# DM1095_USB.net
KiCad netlist of a schematic drawn in Altium Designer
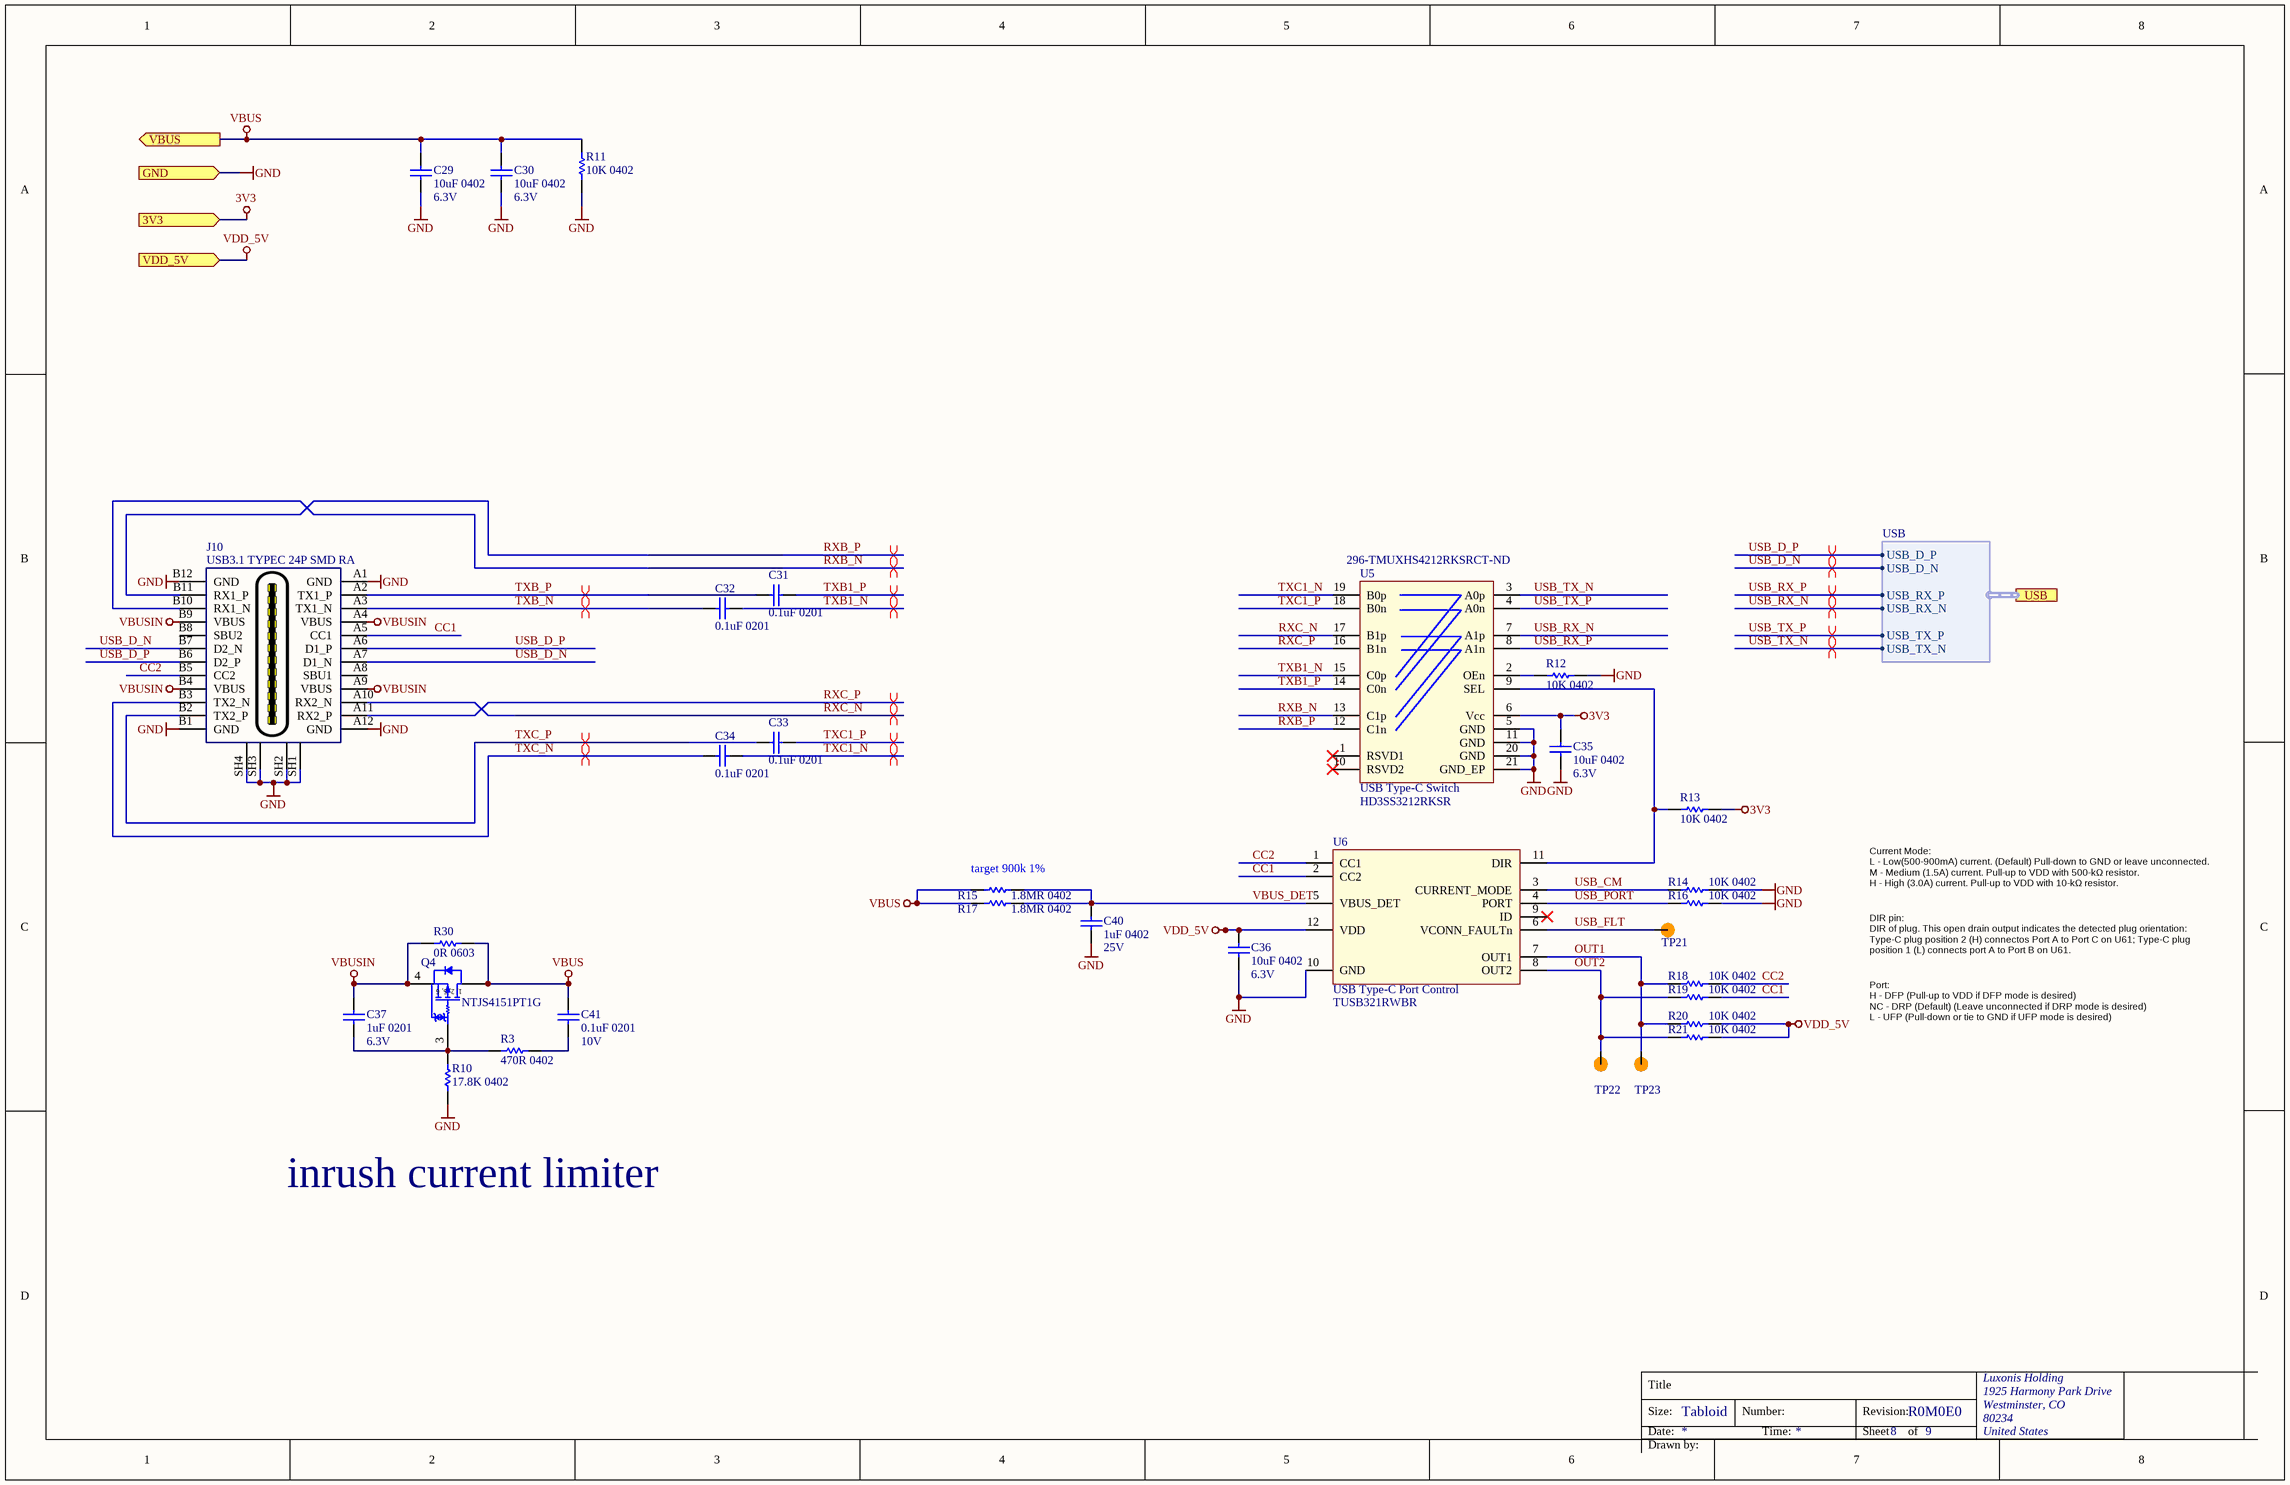
[diagram p0: DM1095_USB.SchDoc]

(export (version "E")
  (design (tool "Eeschema 10.0.6"))
  (components
    (comp (ref "C29")
      (value "10uF 0402")
      (footprint "CAP_Altium_Vault_Generic:CAPC0402(1005)70_L")
      (description "CAP CER 10UF 6.3V X5R 0402 20%")
      (fields (field (name "TOLERANCE") "20%") (field (name "VOLTAGE RATING") "6.3V"))
      (libsource (lib "LuxonisMaster") (part "GRM155R60J106ME15D"))
    )
    (comp (ref "C30")
      (value "10uF 0402")
      (footprint "CAP_Altium_Vault_Generic:CAPC0402(1005)70_L")
      (description "CAP CER 10UF 6.3V X5R 0402 20%")
      (fields (field (name "TOLERANCE") "20%") (field (name "VOLTAGE RATING") "6.3V"))
      (libsource (lib "LuxonisMaster") (part "GRM155R60J106ME15D"))
    )
    (comp (ref "C31")
      (value "0.1uF 0201")
      (footprint "CAP_Altium_Vault_Generic:CAPC0201(0603)33_L")
      (description "CAP CER 0.1UF 10V X5R 0201")
      (fields (field (name "TOLERANCE") "10%") (field (name "VOLTAGE") "10V"))
      (libsource (lib "LuxonisMaster") (part "GRM033R61A104KE15D"))
    )
    (comp (ref "C32")
      (value "0.1uF 0201")
      (footprint "CAP_Altium_Vault_Generic:CAPC0201(0603)33_L")
      (description "CAP CER 0.1UF 10V X5R 0201")
      (fields (field (name "TOLERANCE") "10%") (field (name "VOLTAGE") "10V"))
      (libsource (lib "LuxonisMaster") (part "GRM033R61A104KE15D"))
    )
    (comp (ref "C33")
      (value "0.1uF 0201")
      (footprint "CAP_Altium_Vault_Generic:CAPC0201(0603)33_L")
      (description "CAP CER 0.1UF 10V X5R 0201")
      (fields (field (name "TOLERANCE") "10%") (field (name "VOLTAGE") "10V"))
      (libsource (lib "LuxonisMaster") (part "GRM033R61A104KE15D"))
    )
    (comp (ref "C34")
      (value "0.1uF 0201")
      (footprint "CAP_Altium_Vault_Generic:CAPC0201(0603)33_L")
      (description "CAP CER 0.1UF 10V X5R 0201")
      (fields (field (name "TOLERANCE") "10%") (field (name "VOLTAGE") "10V"))
      (libsource (lib "LuxonisMaster") (part "GRM033R61A104KE15D"))
    )
    (comp (ref "C35")
      (value "10uF 0402")
      (footprint "CAP_Altium_Vault_Generic:CAPC0402(1005)70_L")
      (description "CAP CER 10UF 6.3V X5R 0402 20%")
      (fields (field (name "TOLERANCE") "20%") (field (name "VOLTAGE RATING") "6.3V"))
      (libsource (lib "LuxonisMaster") (part "GRM155R60J106ME15D"))
    )
    (comp (ref "C36")
      (value "10uF 0402")
      (footprint "CAP_Altium_Vault_Generic:CAPC0402(1005)70_L")
      (description "CAP CER 10UF 6.3V X5R 0402 20%")
      (fields (field (name "TOLERANCE") "20%") (field (name "VOLTAGE RATING") "6.3V"))
      (libsource (lib "LuxonisMaster") (part "GRM155R60J106ME15D"))
    )
    (comp (ref "C37")
      (value "1uF 0201")
      (footprint "CAP_Altium_Vault_Generic:CAPC0201(0603)33_N")
      (description "CAP CER 1UF 6.3V X5R 0201 20%")
      (fields (field (name "TOLERANCE") "20%") (field (name "VOLTAGE") "6.3V"))
      (libsource (lib "LuxonisMaster") (part "GRM033R60J105MEA2D"))
    )
    (comp (ref "C40")
      (value "1uF 0402")
      (footprint "CAP_Altium_Vault_Generic:CAPC0402(1005)70_N")
      (description "CAP CER 1UF 25V X5R 0402 10%")
      (fields
        (field (name "TOLERANCE") "10%")
        (field (name "VOLTAGE") "25V")
        (field (name "VOLTAGE RATING") "25V")
      )
      (libsource (lib "LuxonisMaster") (part "GRM155R61E105KA12D"))
    )
    (comp (ref "C41")
      (value "0.1uF 0201")
      (footprint "CAP_Altium_Vault_Generic:CAPC0201(0603)33_N")
      (description "CAP CER 0.1UF 10V X5R 0201")
      (fields (field (name "TOLERANCE") "10%") (field (name "VOLTAGE") "10V"))
      (libsource (lib "LuxonisMaster") (part "GRM033R61A104KE15D"))
    )
    (comp (ref "J10")
      (value "USB3.1 TYPEC 24P SMD RA")
      (footprint "LuxonisMaster:105450-0101")
      (description "CONN RCP USB3.1 TYPEC 24P SMD RA")
      (libsource (lib "LuxonisMaster") (part "105450-0101"))
    )
    (comp (ref "Q4")
      (value "NTJS4151PT1G")
      (footprint "ONSC-SC70-6-419B-02_W_V")
      (description "Trench Power MOSFET, -20 V, -4.2 A, Single P-Channel, 6-Pin SC70, Pb-Free, Tape and Reel")
      (libsource (lib "DM1095") (part "NTJS4151PT1G"))
    )
    (comp (ref "R3")
      (value "470R 0402")
      (footprint "RES_Altium_Vault_Generic:RESC0402(1005)_L")
      (description "RES SMD 470 OHM 1% 1/16W 0402")
      (fields (field (name "TOLERANCE") "1%"))
      (libsource (lib "LuxonisMaster") (part "CRCW0402470RFKED"))
    )
    (comp (ref "R10")
      (value "17.8K 0402")
      (footprint "RES_Altium_Vault_Generic:RESC0402(1005)_L")
      (fields (field (name "TOLERANCE") "1%"))
      (libsource (lib "LuxonisMaster") (part "ERJ-2RKF1782X"))
    )
    (comp (ref "R11")
      (value "10K 0402")
      (footprint "RES_Altium_Vault_Generic:RESC0402(1005)_L")
      (fields (field (name "TOLERANCE") "1%"))
      (libsource (lib "LuxonisMaster") (part "RC0402FR-1310KL"))
    )
    (comp (ref "R12")
      (value "10K 0402")
      (footprint "RES_Altium_Vault_Generic:RESC0402(1005)_L")
      (fields (field (name "TOLERANCE") "1%"))
      (libsource (lib "LuxonisMaster") (part "RC0402FR-1310KL"))
    )
    (comp (ref "R13")
      (value "10K 0402")
      (footprint "RES_Altium_Vault_Generic:RESC0402(1005)_L")
      (fields (field (name "TOLERANCE") "1%"))
      (libsource (lib "LuxonisMaster") (part "RC0402FR-1310KL"))
    )
    (comp (ref "R14")
      (value "10K 0402")
      (footprint "RES_Altium_Vault_Generic:RESC0402(1005)_L")
      (fields (field (name "TOLERANCE") "1%"))
      (libsource (lib "LuxonisMaster") (part "RC0402FR-1310KL"))
    )
    (comp (ref "R15")
      (value "1.8MR 0402")
      (footprint "RES_Altium_Vault_Generic:RESC0402(1005)_L")
      (description "RES SMD 1.8M OHM 1% 1/16W 0402")
      (fields (field (name "TOLERANCE") "1%"))
      (libsource (lib "LuxonisMaster") (part "CRCW04021M80FKED"))
    )
    (comp (ref "R16")
      (value "10K 0402")
      (footprint "RES_Altium_Vault_Generic:RESC0402(1005)_L")
      (fields (field (name "TOLERANCE") "1%"))
      (libsource (lib "LuxonisMaster") (part "RC0402FR-1310KL"))
    )
    (comp (ref "R17")
      (value "1.8MR 0402")
      (footprint "RES_Altium_Vault_Generic:RESC0402(1005)_L")
      (description "RES SMD 1.8M OHM 1% 1/16W 0402")
      (fields (field (name "TOLERANCE") "1%"))
      (libsource (lib "LuxonisMaster") (part "CRCW04021M80FKED"))
    )
    (comp (ref "R18")
      (value "10K 0402")
      (footprint "RES_Altium_Vault_Generic:RESC0402(1005)_L")
      (fields (field (name "TOLERANCE") "1%"))
      (libsource (lib "LuxonisMaster") (part "RC0402FR-1310KL"))
    )
    (comp (ref "R19")
      (value "10K 0402")
      (footprint "RES_Altium_Vault_Generic:RESC0402(1005)_L")
      (fields (field (name "TOLERANCE") "1%"))
      (libsource (lib "LuxonisMaster") (part "RC0402FR-1310KL"))
    )
    (comp (ref "R20")
      (value "10K 0402")
      (footprint "RES_Altium_Vault_Generic:RESC0402(1005)_L")
      (fields (field (name "TOLERANCE") "1%"))
      (libsource (lib "LuxonisMaster") (part "RC0402FR-1310KL"))
    )
    (comp (ref "R21")
      (value "10K 0402")
      (footprint "RES_Altium_Vault_Generic:RESC0402(1005)_L")
      (fields (field (name "TOLERANCE") "1%"))
      (libsource (lib "LuxonisMaster") (part "RC0402FR-1310KL"))
    )
    (comp (ref "R30")
      (value "0R 0603")
      (footprint "RES_Altium_Vault_Generic:RESC0603(1608)_N")
      (fields (field (name "TOLERANCE") "5%"))
      (libsource (lib "LuxonisMaster") (part "CRCW06030000Z0EA"))
    )
    (comp (ref "TP21")
      (value "TP100_200_NS")
      (footprint "LuxonisMaster:TP100_200_NS")
      (libsource (lib "LuxonisMaster") (part "TEST_POINT"))
    )
    (comp (ref "TP22")
      (value "TP100_200_NS")
      (footprint "LuxonisMaster:TP100_200_NS")
      (libsource (lib "LuxonisMaster") (part "TEST_POINT"))
    )
    (comp (ref "TP23")
      (value "TP100_200_NS")
      (footprint "LuxonisMaster:TP100_200_NS")
      (libsource (lib "LuxonisMaster") (part "TEST_POINT"))
    )
    (comp (ref "U5")
      (value "USB Type-C Switch")
      (footprint "LuxonisMaster:HD3SS3212RKSR")
      (description "Differential Multiplexer, 1 Func, 2 Channel, PQCC20")
      (fields
        (field (name "MANUFACTURER PART NUMBER 1") "HD3SS3212RKSR")
        (field (name "SUPPLIER PART NUMBER 2") "296-TMUXHS4212RKSRCT-ND")
      )
      (libsource (lib "LuxonisMaster") (part "HD3SS3212RKSR"))
    )
    (comp (ref "U6")
      (value "USB Type-C Port Control")
      (footprint "LuxonisMaster:TUSB321RWBR")
      (description "IC USB PORT CONTROL TYPE-C 12X2Q")
      (fields (field (name "MANUFACTURER PART NUMBER 1") "TUSB321RWBR"))
      (libsource (lib "LuxonisMaster") (part "TUSB321RWBR"))
    )
  )
  (nets
    (net (code "2") (name "/CC1") (class "Default")
      (node (ref "J10") (pin "A5") (pinfunction "CC1_A5") (pintype "passive"))
      (node (ref "R19") (pin "2") (pinfunction "2_2") (pintype "passive"))
      (node (ref "U6") (pin "2") (pinfunction "CC2_2") (pintype "passive"))
    )
    (net (code "3") (name "/CC2") (class "Default")
      (node (ref "J10") (pin "B5") (pinfunction "CC2_B5") (pintype "passive"))
      (node (ref "R18") (pin "2") (pinfunction "2_2") (pintype "passive"))
      (node (ref "U6") (pin "1") (pinfunction "CC1_1") (pintype "passive"))
    )
    (net (code "4") (name "/OUT1") (class "Default")
      (node (ref "R18") (pin "1") (pinfunction "1_1") (pintype "passive"))
      (node (ref "R20") (pin "1") (pinfunction "1_1") (pintype "passive"))
      (node (ref "TP23") (pin "1") (pintype "passive"))
      (node (ref "U6") (pin "7") (pinfunction "OUT1_7") (pintype "passive"))
    )
    (net (code "5") (name "/OUT2") (class "Default")
      (node (ref "R19") (pin "1") (pinfunction "1_1") (pintype "passive"))
      (node (ref "R21") (pin "1") (pinfunction "1_1") (pintype "passive"))
      (node (ref "TP22") (pin "1") (pintype "passive"))
      (node (ref "U6") (pin "8") (pinfunction "OUT2_8") (pintype "passive"))
    )
    (net (code "6") (name "/RXB_N") (class "Default")
      (node (ref "J10") (pin "B10") (pinfunction "RX1_N_B10") (pintype "passive"))
      (node (ref "U5") (pin "13") (pinfunction "C1p_13") (pintype "passive"))
    )
    (net (code "7") (name "/RXB_P") (class "Default")
      (node (ref "J10") (pin "B11") (pinfunction "RX1_P_B11") (pintype "passive"))
      (node (ref "U5") (pin "12") (pinfunction "C1n_12") (pintype "passive"))
    )
    (net (code "8") (name "/RXC_N") (class "Default")
      (node (ref "J10") (pin "A10") (pinfunction "RX2_N_A10") (pintype "passive"))
      (node (ref "U5") (pin "17") (pinfunction "B1p_17") (pintype "passive"))
    )
    (net (code "9") (name "/RXC_P") (class "Default")
      (node (ref "J10") (pin "A11") (pinfunction "RX2_P_A11") (pintype "passive"))
      (node (ref "U5") (pin "16") (pinfunction "B1n_16") (pintype "passive"))
    )
    (net (code "10") (name "/TXB1_N") (class "Default")
      (node (ref "C32") (pin "2") (pinfunction "2_2") (pintype "passive"))
      (node (ref "U5") (pin "15") (pinfunction "C0p_15") (pintype "passive"))
    )
    (net (code "11") (name "/TXB1_P") (class "Default")
      (node (ref "C31") (pin "2") (pinfunction "2_2") (pintype "passive"))
      (node (ref "U5") (pin "14") (pinfunction "C0n_14") (pintype "passive"))
    )
    (net (code "12") (name "/TXB_N") (class "Default")
      (node (ref "C32") (pin "1") (pinfunction "1_1") (pintype "passive"))
      (node (ref "J10") (pin "A3") (pinfunction "TX1_N_A3") (pintype "passive"))
    )
    (net (code "13") (name "/TXB_P") (class "Default")
      (node (ref "C31") (pin "1") (pinfunction "1_1") (pintype "passive"))
      (node (ref "J10") (pin "A2") (pinfunction "TX1_P_A2") (pintype "passive"))
    )
    (net (code "14") (name "/TXC1_N") (class "Default")
      (node (ref "C34") (pin "2") (pinfunction "2_2") (pintype "passive"))
      (node (ref "U5") (pin "19") (pinfunction "B0p_19") (pintype "passive"))
    )
    (net (code "15") (name "/TXC1_P") (class "Default")
      (node (ref "C33") (pin "2") (pinfunction "2_2") (pintype "passive"))
      (node (ref "U5") (pin "18") (pinfunction "B0n_18") (pintype "passive"))
    )
    (net (code "16") (name "/TXC_N") (class "Default")
      (node (ref "C34") (pin "1") (pinfunction "1_1") (pintype "passive"))
      (node (ref "J10") (pin "B3") (pinfunction "TX2_N_B3") (pintype "passive"))
    )
    (net (code "17") (name "/TXC_P") (class "Default")
      (node (ref "C33") (pin "1") (pinfunction "1_1") (pintype "passive"))
      (node (ref "J10") (pin "B2") (pinfunction "TX2_P_B2") (pintype "passive"))
    )
    (net (code "18") (name "/USB_CM") (class "Default")
      (node (ref "R14") (pin "1") (pinfunction "1_1") (pintype "passive"))
      (node (ref "U6") (pin "3") (pinfunction "CURRENT_MODE_3") (pintype "passive"))
    )
    (net (code "19") (name "/USB_D_N") (class "Default")
      (node (ref "J10") (pin "A7") (pinfunction "D1_N_A7") (pintype "passive"))
      (node (ref "J10") (pin "B7") (pinfunction "D2_N_B7") (pintype "passive"))
    )
    (net (code "20") (name "/USB_D_P") (class "Default")
      (node (ref "J10") (pin "A6") (pinfunction "D1_P_A6") (pintype "passive"))
      (node (ref "J10") (pin "B6") (pinfunction "D2_P_B6") (pintype "passive"))
    )
    (net (code "21") (name "/USB_FLT") (class "Default")
      (node (ref "TP21") (pin "1") (pintype "passive"))
      (node (ref "U6") (pin "6") (pinfunction "VCONN_FAULTn_6") (pintype "passive"))
    )
    (net (code "22") (name "/USB_PORT") (class "Default")
      (node (ref "R16") (pin "1") (pinfunction "1_1") (pintype "passive"))
      (node (ref "U6") (pin "4") (pinfunction "PORT_4") (pintype "passive"))
    )
    (net (code "23") (name "/USB_RX_N") (class "Default")
      (node (ref "U5") (pin "7") (pinfunction "A1p_7") (pintype "passive"))
    )
    (net (code "24") (name "/USB_RX_P") (class "Default")
      (node (ref "U5") (pin "8") (pinfunction "A1n_8") (pintype "passive"))
    )
    (net (code "25") (name "/USB_TX_N") (class "Default")
      (node (ref "U5") (pin "3") (pinfunction "A0p_3") (pintype "passive"))
    )
    (net (code "26") (name "/USB_TX_P") (class "Default")
      (node (ref "U5") (pin "4") (pinfunction "A0n_4") (pintype "passive"))
    )
    (net (code "27") (name "/VBUS_DET") (class "Default")
      (node (ref "C40") (pin "2") (pinfunction "2_2") (pintype "passive"))
      (node (ref "R15") (pin "2") (pinfunction "2_2") (pintype "passive"))
      (node (ref "R17") (pin "2") (pinfunction "2_2") (pintype "passive"))
      (node (ref "U6") (pin "5") (pinfunction "VBUS_DET_5") (pintype "passive"))
    )
    (net (code "29") (name "3V3") (class "Default")
      (node (ref "C35") (pin "2") (pinfunction "2_2") (pintype "passive"))
      (node (ref "R13") (pin "2") (pinfunction "2_2") (pintype "passive"))
      (node (ref "U5") (pin "6") (pinfunction "Vcc_6") (pintype "passive"))
    )
    (net (code "30") (name "GND") (class "Default")
      (node (ref "C29") (pin "1") (pinfunction "1_1") (pintype "passive"))
      (node (ref "C30") (pin "1") (pinfunction "1_1") (pintype "passive"))
      (node (ref "C35") (pin "1") (pinfunction "1_1") (pintype "passive"))
      (node (ref "C36") (pin "1") (pinfunction "1_1") (pintype "passive"))
      (node (ref "C40") (pin "1") (pinfunction "1_1") (pintype "passive"))
      (node (ref "J10") (pin "A1") (pinfunction "GND_A1") (pintype "passive"))
      (node (ref "J10") (pin "A12") (pinfunction "GND_A12") (pintype "passive"))
      (node (ref "J10") (pin "B1") (pinfunction "GND_B1") (pintype "passive"))
      (node (ref "J10") (pin "B12") (pinfunction "GND_B12") (pintype "passive"))
      (node (ref "J10") (pin "SH1") (pinfunction "SH_SH1") (pintype "passive"))
      (node (ref "J10") (pin "SH2") (pinfunction "SH_SH2") (pintype "passive"))
      (node (ref "J10") (pin "SH3") (pinfunction "SH_SH3") (pintype "passive"))
      (node (ref "J10") (pin "SH4") (pinfunction "SH_SH4") (pintype "passive"))
      (node (ref "R10") (pin "1") (pinfunction "1_1") (pintype "passive"))
      (node (ref "R11") (pin "1") (pinfunction "1_1") (pintype "passive"))
      (node (ref "R12") (pin "2") (pinfunction "2_2") (pintype "passive"))
      (node (ref "R14") (pin "2") (pinfunction "2_2") (pintype "passive"))
      (node (ref "R16") (pin "2") (pinfunction "2_2") (pintype "passive"))
      (node (ref "U5") (pin "11") (pinfunction "GND_11") (pintype "passive"))
      (node (ref "U5") (pin "20") (pinfunction "GND_20") (pintype "passive"))
      (node (ref "U5") (pin "21") (pinfunction "GND_EP_21") (pintype "passive"))
      (node (ref "U5") (pin "5") (pinfunction "GND_5") (pintype "passive"))
      (node (ref "U6") (pin "10") (pinfunction "GND_10") (pintype "passive"))
    )
    (net (code "31") (name "Net-(C41-Pad1)") (class "Default")
      (node (ref "C41") (pin "1") (pinfunction "1_1") (pintype "passive"))
      (node (ref "R3") (pin "2") (pinfunction "2_2") (pintype "passive"))
    )
    (net (code "32") (name "Net-(Q4-G)") (class "Default")
      (node (ref "C37") (pin "1") (pinfunction "1_1") (pintype "passive"))
      (node (ref "Q4") (pin "3") (pinfunction "G_3") (pintype "passive"))
      (node (ref "R10") (pin "2") (pinfunction "2_2") (pintype "passive"))
      (node (ref "R3") (pin "1") (pinfunction "1_1") (pintype "passive"))
    )
    (net (code "33") (name "Net-(U5-OEn)") (class "Default")
      (node (ref "R12") (pin "1") (pinfunction "1_1") (pintype "passive"))
      (node (ref "U5") (pin "2") (pinfunction "OEn_2") (pintype "passive"))
    )
    (net (code "34") (name "Net-(U5-SEL)") (class "Default")
      (node (ref "R13") (pin "1") (pinfunction "1_1") (pintype "passive"))
      (node (ref "U5") (pin "9") (pinfunction "SEL_9") (pintype "passive"))
      (node (ref "U6") (pin "11") (pinfunction "DIR_11") (pintype "passive"))
    )
    (net (code "35") (name "VBUS") (class "Default")
      (node (ref "C29") (pin "2") (pinfunction "2_2") (pintype "passive"))
      (node (ref "C30") (pin "2") (pinfunction "2_2") (pintype "passive"))
      (node (ref "C41") (pin "2") (pinfunction "2_2") (pintype "passive"))
      (node (ref "Q4") (pin "1") (pinfunction "D_1") (pintype "passive"))
      (node (ref "Q4") (pin "2") (pinfunction "D_2") (pintype "passive"))
      (node (ref "Q4") (pin "5") (pinfunction "D_5") (pintype "passive"))
      (node (ref "Q4") (pin "6") (pinfunction "D_6") (pintype "passive"))
      (node (ref "R11") (pin "2") (pinfunction "2_2") (pintype "passive"))
      (node (ref "R15") (pin "1") (pinfunction "1_1") (pintype "passive"))
      (node (ref "R17") (pin "1") (pinfunction "1_1") (pintype "passive"))
      (node (ref "R30") (pin "2") (pinfunction "2_2") (pintype "passive"))
    )
    (net (code "36") (name "VBUSIN") (class "Default")
      (node (ref "C37") (pin "2") (pinfunction "2_2") (pintype "passive"))
      (node (ref "J10") (pin "A4") (pinfunction "VBUS_A4") (pintype "passive"))
      (node (ref "J10") (pin "A9") (pinfunction "VBUS_A9") (pintype "passive"))
      (node (ref "J10") (pin "B4") (pinfunction "VBUS_B4") (pintype "passive"))
      (node (ref "J10") (pin "B9") (pinfunction "VBUS_B9") (pintype "passive"))
      (node (ref "Q4") (pin "4") (pinfunction "S_4") (pintype "passive"))
      (node (ref "R30") (pin "1") (pinfunction "1_1") (pintype "passive"))
    )
    (net (code "37") (name "VDD_5V") (class "Default")
      (node (ref "C36") (pin "2") (pinfunction "2_2") (pintype "passive"))
      (node (ref "R20") (pin "2") (pinfunction "2_2") (pintype "passive"))
      (node (ref "R21") (pin "2") (pinfunction "2_2") (pintype "passive"))
      (node (ref "U6") (pin "12") (pinfunction "VDD_12") (pintype "passive"))
    )
    (net (code "38") (name "unconnected-(J10-SBU1-PadA8)") (class "Default")
      (node (ref "J10") (pin "A8") (pinfunction "SBU1_A8") (pintype "passive"))
    )
    (net (code "39") (name "unconnected-(J10-SBU2-PadB8)") (class "Default")
      (node (ref "J10") (pin "B8") (pinfunction "SBU2_B8") (pintype "passive"))
    )
    (net (code "40") (name "unconnected-(U5-RSVD1-Pad1)") (class "Default")
      (node (ref "U5") (pin "1") (pinfunction "RSVD1_1") (pintype "passive+no_connect"))
    )
    (net (code "41") (name "unconnected-(U5-RSVD2-Pad10)") (class "Default")
      (node (ref "U5") (pin "10") (pinfunction "RSVD2_10") (pintype "passive+no_connect"))
    )
    (net (code "42") (name "unconnected-(U6-ID-Pad9)") (class "Default")
      (node (ref "U6") (pin "9") (pinfunction "ID_9") (pintype "passive+no_connect"))
    )
  )
)
